# JST_LED.net
KiCad netlist of a schematic drawn in Altium Designer
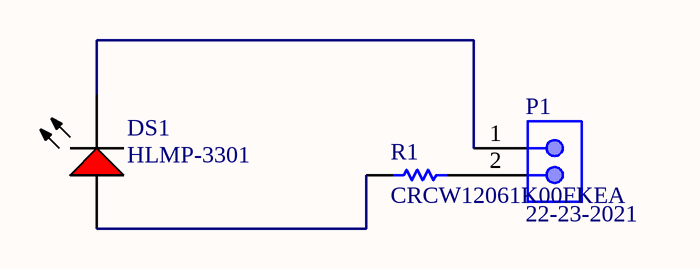
[diagram p0: JST_LED.SchDoc]

(export (version "E")
  (design (tool "Eeschema 10.0.6"))
  (components
    (comp (ref "DS1")
      (value "HLMP-3301")
      (footprint "AVAG-HLMP-3301-2")
      (description "T-1 3/4 (5 mm) Diffused LED Lamp, 1.9 V, -40 to 100 degC, 2-Pin THD, RoHS, Bulk")
      (fields (field (name "MANUFACTURER") "Avago"))
      (libsource (lib "Altium Content Vault") (part "LED-RED-K1A2-2"))
    )
    (comp (ref "P1")
      (value "22-23-2021")
      (footprint "MOLX-22-23-2021_V")
      (libsource (lib "Altium Content Vault") (part "CN-1P-M-R2"))
    )
    (comp (ref "R1")
      (value "CRCW12061K00FKEA")
      (footprint "RESC3216X60X45ML15T20")
      (description "Chip Resistor, 1 KOhm, +/- 1%, 0.25 W, -55 to 155 degC, 1206 (3216 Metric), RoHS, Tape and Reel")
      (fields (field (name "MANUFACTURER") "Vishay Semiconductor") (field (name "TOLERANCE") "1%"))
      (libsource (lib "Altium Content Vault") (part "RES-2"))
    )
  )
  (nets
    (net (code "1") (name "Net-(DS1-A)") (class "Default")
      (node (ref "DS1") (pin "2") (pinfunction "A_2") (pintype "passive"))
      (node (ref "R1") (pin "1") (pinfunction "1_1") (pintype "passive"))
    )
    (net (code "2") (name "Net-(DS1-K)") (class "Default")
      (node (ref "DS1") (pin "1") (pinfunction "K_1") (pintype "passive"))
      (node (ref "P1") (pin "1") (pinfunction "1_1") (pintype "passive"))
    )
    (net (code "3") (name "Net-(P1-Pad2)") (class "Default")
      (node (ref "P1") (pin "2") (pinfunction "2_2") (pintype "passive"))
      (node (ref "R1") (pin "2") (pinfunction "2_2") (pintype "passive"))
    )
  )
)
